# 04_-_CIRCUIT.net
KiCad netlist of a schematic drawn in Altium Designer
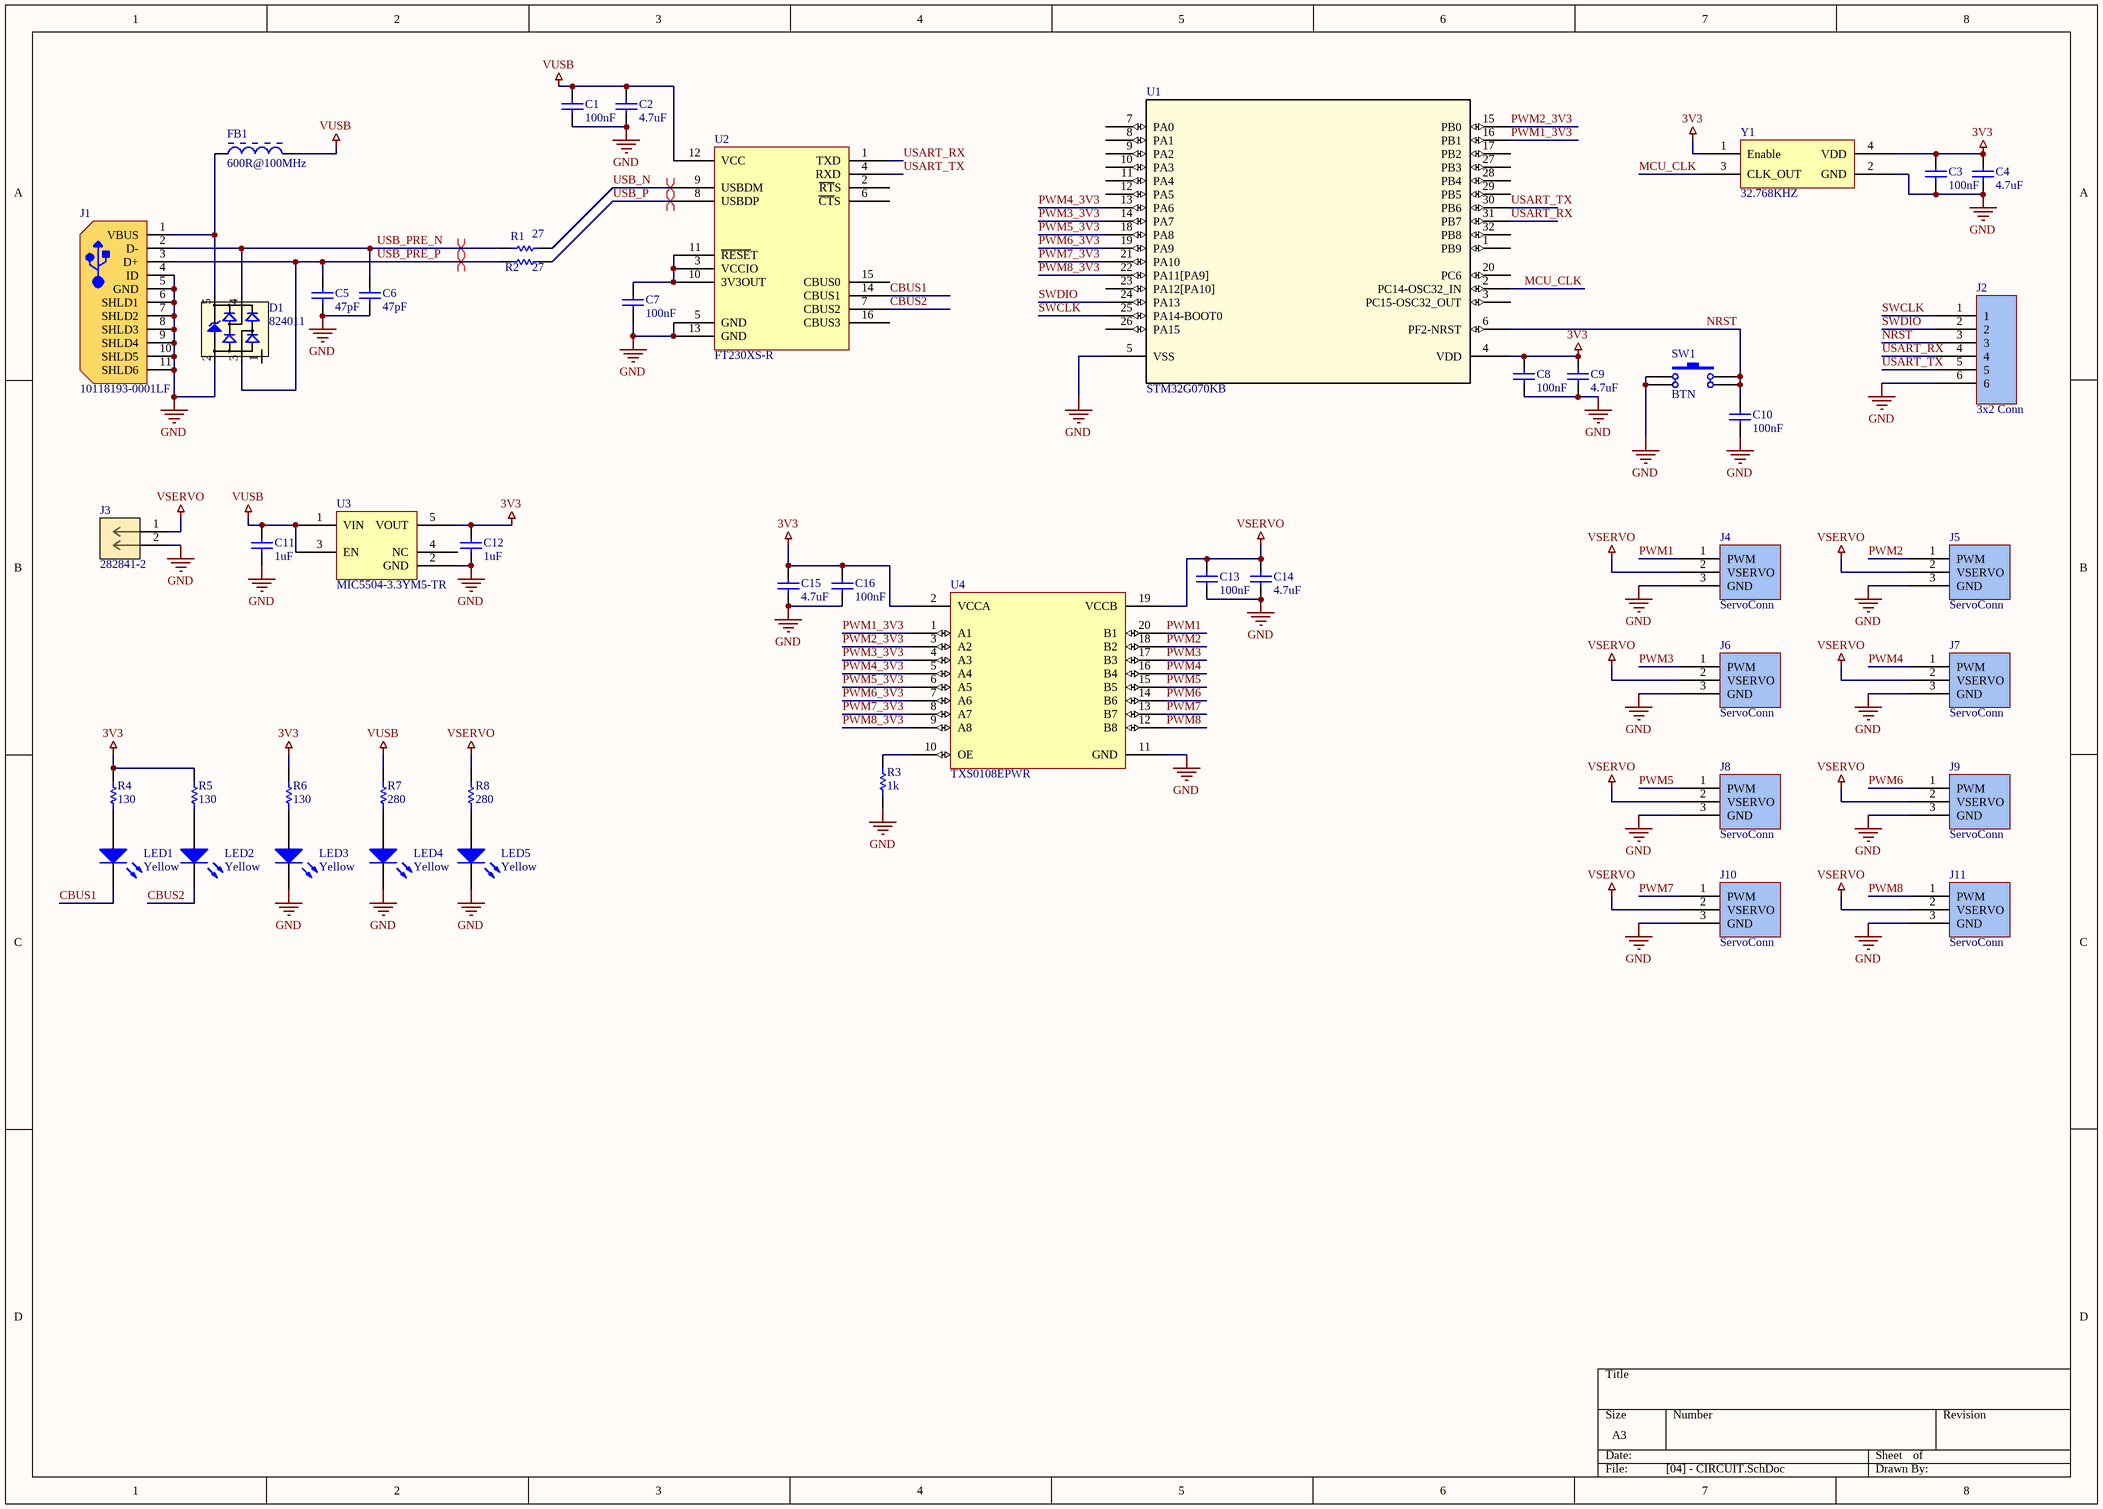
[diagram p0: [04] - CIRCUIT.SchDoc]

(export (version "E")
  (design (tool "Eeschema 10.0.6"))
  (components
    (comp (ref "C1")
      (value "100nF")
      (footprint "CAPC2012X10N")
      (description "CAP CER 0.1UF 100V X7R 0805")
      (libsource (lib "roboARM") (part "GCD21BR72A104KA01L"))
    )
    (comp (ref "C2")
      (value "4.7uF")
      (footprint "CAPC2012X10N")
      (description "Cap Ceramic 4.7uF 50V X5R 10% SMD 0805 85C Embossed T/R")
      (fields (field (name "TOLERANCE") "10%"))
      (libsource (lib "*") (part "GRM21BR61H475KE51L"))
    )
    (comp (ref "C3")
      (value "100nF")
      (footprint "CAPC2012X10N")
      (description "CAP CER 0.1UF 100V X7R 0805")
      (libsource (lib "roboARM") (part "GCD21BR72A104KA01L"))
    )
    (comp (ref "C4")
      (value "4.7uF")
      (footprint "CAPC2012X10N")
      (description "Cap Ceramic 4.7uF 50V X5R 10% SMD 0805 85C Embossed T/R")
      (fields (field (name "TOLERANCE") "10%"))
      (libsource (lib "*") (part "GRM21BR61H475KE51L"))
    )
    (comp (ref "C5")
      (value "47pF")
      (footprint "CAPC2012X10N")
      (fields (field (name "VOLTAGE") "200V") (field (name "TOLERANCE") "5%"))
      (libsource (lib "roboARM") (part "GRM21A5C2D470JW01D"))
    )
    (comp (ref "C6")
      (value "47pF")
      (footprint "CAPC2012X10N")
      (fields (field (name "VOLTAGE") "200V") (field (name "TOLERANCE") "5%"))
      (libsource (lib "roboARM") (part "GRM21A5C2D470JW01D"))
    )
    (comp (ref "C7")
      (value "100nF")
      (footprint "CAPC2012X10N")
      (description "CAP CER 0.1UF 100V X7R 0805")
      (libsource (lib "roboARM") (part "GCD21BR72A104KA01L"))
    )
    (comp (ref "C8")
      (value "100nF")
      (footprint "CAPC2012X10N")
      (description "CAP CER 0.1UF 100V X7R 0805")
      (libsource (lib "roboARM") (part "GCD21BR72A104KA01L"))
    )
    (comp (ref "C9")
      (value "4.7uF")
      (footprint "CAPC2012X10N")
      (description "Cap Ceramic 4.7uF 50V X5R 10% SMD 0805 85C Embossed T/R")
      (fields (field (name "TOLERANCE") "10%"))
      (libsource (lib "*") (part "GRM21BR61H475KE51L"))
    )
    (comp (ref "C10")
      (value "100nF")
      (footprint "CAPC2012X10N")
      (description "CAP CER 0.1UF 100V X7R 0805")
      (libsource (lib "roboARM") (part "GCD21BR72A104KA01L"))
    )
    (comp (ref "C11")
      (value "CL21B105KOFNNNG")
      (footprint "CAPC2012X10N")
      (description "Cap Ceramic 1uF 16V X7R 10% SMD 0805 125C Embossed T/R")
      (fields
        (field (name "MANUFACTURER") "Samsung")
        (field (name "TOLERANCE") "10%")
        (field (name "CAPACITANCE") "1uF")
      )
      (libsource (lib "roboARM") (part "CL21B105KOFNNNG"))
    )
    (comp (ref "C12")
      (value "CL21B105KOFNNNG")
      (footprint "CAPC2012X10N")
      (description "Cap Ceramic 1uF 16V X7R 10% SMD 0805 125C Embossed T/R")
      (fields
        (field (name "MANUFACTURER") "Samsung")
        (field (name "TOLERANCE") "10%")
        (field (name "CAPACITANCE") "1uF")
      )
      (libsource (lib "roboARM") (part "CL21B105KOFNNNG"))
    )
    (comp (ref "C13")
      (value "100nF")
      (footprint "CAPC2012X10N")
      (description "CAP CER 0.1UF 100V X7R 0805")
      (libsource (lib "roboARM") (part "GCD21BR72A104KA01L"))
    )
    (comp (ref "C14")
      (value "4.7uF")
      (footprint "CAPC2012X10N")
      (description "Cap Ceramic 4.7uF 50V X5R 10% SMD 0805 85C Embossed T/R")
      (fields (field (name "TOLERANCE") "10%"))
      (libsource (lib "*") (part "GRM21BR61H475KE51L"))
    )
    (comp (ref "C15")
      (value "4.7uF")
      (footprint "CAPC2012X10N")
      (description "Cap Ceramic 4.7uF 50V X5R 10% SMD 0805 85C Embossed T/R")
      (fields (field (name "TOLERANCE") "10%"))
      (libsource (lib "*") (part "GRM21BR61H475KE51L"))
    )
    (comp (ref "C16")
      (value "100nF")
      (footprint "CAPC2012X10N")
      (description "CAP CER 0.1UF 100V X7R 0805")
      (libsource (lib "roboARM") (part "GCD21BR72A104KA01L"))
    )
    (comp (ref "D1")
      (value "824011")
      (footprint "SOT23_5L")
      (description "TVS Diode WE-TVS-HS, VRWM=5V")
      (fields (field (name "MANUFACTURER") "Wuerth Elektronik"))
      (libsource (lib "roboARM") (part "CMP-1474-00002-1"))
    )
    (comp (ref "FB1")
      (value "600R@100MHz")
      (footprint "LIRD-MI0805K601R-10-2_V")
      (description "FERRITE BEAD 600 OHM 0805 1LN")
      (libsource (lib "roboARM") (part "MI0805K601R-10"))
    )
    (comp (ref "J1")
      (value "10118193-0001LF")
      (footprint "FCI-10118193-0001LF-5_V")
      (description "Micro USB B Type Receptacle, -55 to 85 degC, 5-Pin SMD, RoHS, Tape and Reel")
      (fields (field (name "MANUFACTURER") "FCI"))
      (libsource (lib "roboARM") (part "CMP-2000-05119-1"))
    )
    (comp (ref "J2")
      (value "3x2 Conn")
      (footprint "61200621721")
      (libsource (lib "roboARM") (part "61200621721"))
    )
    (comp (ref "J3")
      (value "282841-2")
      (footprint "Clema")
      (description "No Description Available")
      (fields (field (name "COPYRIGHT") "Copyright (C) 2016 Accelerated Designs. All rights reserved"))
      (libsource (lib "roboARM") (part "282841-2"))
    )
    (comp (ref "J4")
      (value "ServoConn")
      (footprint "3_POS_PIN")
      (description "CONN HEADER VERT 3POS 2.54MM")
      (libsource (lib "roboARM") (part "PR20203VBNN"))
    )
    (comp (ref "J5")
      (value "ServoConn")
      (footprint "3_POS_PIN")
      (description "CONN HEADER VERT 3POS 2.54MM")
      (libsource (lib "roboARM") (part "PR20203VBNN"))
    )
    (comp (ref "J6")
      (value "ServoConn")
      (footprint "3_POS_PIN")
      (description "CONN HEADER VERT 3POS 2.54MM")
      (libsource (lib "roboARM") (part "PR20203VBNN"))
    )
    (comp (ref "J7")
      (value "ServoConn")
      (footprint "3_POS_PIN")
      (description "CONN HEADER VERT 3POS 2.54MM")
      (libsource (lib "roboARM") (part "PR20203VBNN"))
    )
    (comp (ref "J8")
      (value "ServoConn")
      (footprint "3_POS_PIN")
      (description "CONN HEADER VERT 3POS 2.54MM")
      (libsource (lib "roboARM") (part "PR20203VBNN"))
    )
    (comp (ref "J9")
      (value "ServoConn")
      (footprint "3_POS_PIN")
      (description "CONN HEADER VERT 3POS 2.54MM")
      (libsource (lib "roboARM") (part "PR20203VBNN"))
    )
    (comp (ref "J10")
      (value "ServoConn")
      (footprint "3_POS_PIN")
      (description "CONN HEADER VERT 3POS 2.54MM")
      (libsource (lib "roboARM") (part "PR20203VBNN"))
    )
    (comp (ref "J11")
      (value "ServoConn")
      (footprint "3_POS_PIN")
      (description "CONN HEADER VERT 3POS 2.54MM")
      (libsource (lib "roboARM") (part "PR20203VBNN"))
    )
    (comp (ref "LED1")
      (value "Yellow")
      (footprint "LED_0805")
      (description "SMD mono-color Chip LED, WL-SMCW, Yellow")
      (fields (field (name "MANUFACTURER") "Wuerth Elektronik") (field (name "PARTNUMBER") "150080YS75000"))
      (libsource (lib "roboARM") (part "CMP-1426-00012-1"))
    )
    (comp (ref "LED2")
      (value "Yellow")
      (footprint "LED_0805")
      (description "SMD mono-color Chip LED, WL-SMCW, Yellow")
      (fields (field (name "MANUFACTURER") "Wuerth Elektronik") (field (name "PARTNUMBER") "150080YS75000"))
      (libsource (lib "roboARM") (part "CMP-1426-00012-1"))
    )
    (comp (ref "LED3")
      (value "Yellow")
      (footprint "LED_0805")
      (description "SMD mono-color Chip LED, WL-SMCW, Yellow")
      (fields (field (name "MANUFACTURER") "Wuerth Elektronik") (field (name "PARTNUMBER") "150080YS75000"))
      (libsource (lib "roboARM") (part "CMP-1426-00012-1"))
    )
    (comp (ref "LED4")
      (value "Yellow")
      (footprint "LED_0805")
      (description "SMD mono-color Chip LED, WL-SMCW, Yellow")
      (fields (field (name "MANUFACTURER") "Wuerth Elektronik") (field (name "PARTNUMBER") "150080YS75000"))
      (libsource (lib "roboARM") (part "CMP-1426-00012-1"))
    )
    (comp (ref "LED5")
      (value "Yellow")
      (footprint "LED_0805")
      (description "SMD mono-color Chip LED, WL-SMCW, Yellow")
      (fields (field (name "MANUFACTURER") "Wuerth Elektronik") (field (name "PARTNUMBER") "150080YS75000"))
      (libsource (lib "roboARM") (part "CMP-1426-00012-1"))
    )
    (comp (ref "R1")
      (value "27")
      (footprint "RESC2012X07N")
      (description "RES 27 OHM 1/8W 1% 0805")
      (fields (field (name "TOLERANCE") "1%"))
      (libsource (lib "roboARM") (part "RMCF0805FT27R0"))
    )
    (comp (ref "R2")
      (value "27")
      (footprint "RESC2012X07N")
      (description "RES 27 OHM 1/8W 1% 0805")
      (fields (field (name "TOLERANCE") "1%"))
      (libsource (lib "roboARM") (part "RMCF0805FT27R0"))
    )
    (comp (ref "R3")
      (value "1k")
      (footprint "RESC2012X07N")
      (description "RES 1K OHM 5% 1/8W 0805")
      (fields
        (field (name "MANUFACTURER") "Stackpole Electronics")
        (field (name "MANUFACTURER PART NUMBER") "RMCF0805JT1K00")
      )
      (libsource (lib "roboARM") (part "RMCF0805JT1K00"))
    )
    (comp (ref "R4")
      (value "130")
      (footprint "RESC2012X07N")
      (description "Res Thick Film 0805 130 Ohm 1% 0.125W(1/8W) ±100ppm/C Pad SMD Automotive T/R")
      (fields (field (name "TOLERANCE") "1%"))
      (libsource (lib "roboARM") (part "RMCF0805FT130R"))
    )
    (comp (ref "R5")
      (value "130")
      (footprint "RESC2012X07N")
      (description "Res Thick Film 0805 130 Ohm 1% 0.125W(1/8W) ±100ppm/C Pad SMD Automotive T/R")
      (fields (field (name "TOLERANCE") "1%"))
      (libsource (lib "roboARM") (part "RMCF0805FT130R"))
    )
    (comp (ref "R6")
      (value "130")
      (footprint "RESC2012X07N")
      (description "Res Thick Film 0805 130 Ohm 1% 0.125W(1/8W) ±100ppm/C Pad SMD Automotive T/R")
      (fields (field (name "TOLERANCE") "1%"))
      (libsource (lib "roboARM") (part "RMCF0805FT130R"))
    )
    (comp (ref "R7")
      (value "280")
      (footprint "RESC2012X07N")
      (description "Res Thick Film 0805 280 Ohm 1% 0.125W(1/8W) ±100ppm/C Pad SMD Automotive T/R")
      (fields (field (name "TOLERANCE") "1%"))
      (libsource (lib "roboARM") (part "RMCF0805FT280R"))
    )
    (comp (ref "R8")
      (value "280")
      (description "Res Thick Film 0805 280 Ohm 1% 0.125W(1/8W) ±100ppm/C Pad SMD Automotive T/R")
      (fields (field (name "TOLERANCE") "1%"))
      (libsource (lib "roboARM") (part "RMCF0805FT280R"))
    )
    (comp (ref "SW1")
      (value "BTN")
      (footprint "Button")
      (description "INWALL LENS COVER , WHITE , 6 (")
      (fields
        (field (name "MANUFACTURER") "ITT C&K")
        (field (name "MANUFACTURER PART NUMBER") "PTS647SK70SMTR2LFS")
      )
      (libsource (lib "roboARM") (part "PTS647SK70SMTR2LFS"))
    )
    (comp (ref "U1")
      (value "STM32G070KB")
      (footprint "LQFP-32")
      (fields
        (field (name "MANUFACTURER_PART_NUMBER") "STM32G0_LQFP32_T1")
        (field (name "COPYRIGHT") "Copyright (C) 2016 Accelerated Designs. All rights reserved")
      )
      (libsource (lib "roboARM") (part "STM32G070KB"))
    )
    (comp (ref "U2")
      (value "FT230XS-R")
      (footprint "SOP64P600X175-16N")
      (description "IC USB SERIAL BASIC UART 16SSOP")
      (libsource (lib "roboARM") (part "FT230XS-R"))
    )
    (comp (ref "U3")
      (value "MIC5504-3.3YM5-TR")
      (footprint "SOT95P280X145-5N")
      (description "LDO VOLT REG, 0.3A, 3.3V, SOT-23-5")
      (libsource (lib "roboARM") (part "MIC5504-3.3YM5-TR"))
    )
    (comp (ref "U4")
      (value "TXS0108EPWR")
      (footprint "TSOP65P640X120-20N")
      (description "TRANSLATOR, VOLTAGE, 8BIT, 20TSSOP")
      (libsource (lib "roboARM") (part "TXS0108EPWR"))
    )
    (comp (ref "Y1")
      (value "32.768KHZ")
      (footprint "KX251")
      (description "OSCILLATOR XO 32.768KHZ CMOS SMD")
      (libsource (lib "roboARM") (part "KX2511A0032.768000"))
    )
  )
  (nets
    (net (code "1") (name "/CBUS1") (class "Default")
      (node (ref "LED1") (pin "1") (pinfunction "K_1") (pintype "passive"))
      (node (ref "U2") (pin "14") (pinfunction "CBUS1_14") (pintype "passive"))
    )
    (net (code "2") (name "/CBUS2") (class "Default")
      (node (ref "LED2") (pin "1") (pinfunction "K_1") (pintype "passive"))
      (node (ref "U2") (pin "7") (pinfunction "CBUS2_7") (pintype "passive"))
    )
    (net (code "3") (name "/MCU_CLK") (class "Default")
      (node (ref "U1") (pin "2") (pinfunction "PC14-OSC32_IN_2") (pintype "bidirectional"))
      (node (ref "Y1") (pin "3") (pinfunction "CLK_OUT_3") (pintype "passive"))
    )
    (net (code "4") (name "/NRST") (class "Default")
      (node (ref "C10") (pin "2") (pinfunction "2_2") (pintype "passive"))
      (node (ref "J2") (pin "3") (pinfunction "3_3") (pintype "passive"))
      (node (ref "SW1") (pin "3") (pinfunction "2_3") (pintype "passive"))
      (node (ref "SW1") (pin "4") (pinfunction "3_4") (pintype "passive"))
      (node (ref "U1") (pin "6") (pinfunction "PF2-NRST_6") (pintype "bidirectional"))
    )
    (net (code "5") (name "/PWM1") (class "Default")
      (node (ref "J4") (pin "1") (pinfunction "PWM_1") (pintype "passive"))
      (node (ref "U4") (pin "20") (pinfunction "B1_20") (pintype "bidirectional"))
    )
    (net (code "6") (name "/PWM1_3V3") (class "Default")
      (node (ref "U1") (pin "16") (pinfunction "PB1_16") (pintype "bidirectional"))
      (node (ref "U4") (pin "1") (pinfunction "A1_1") (pintype "bidirectional"))
    )
    (net (code "7") (name "/PWM2") (class "Default")
      (node (ref "J5") (pin "1") (pinfunction "PWM_1") (pintype "passive"))
      (node (ref "U4") (pin "18") (pinfunction "B2_18") (pintype "bidirectional"))
    )
    (net (code "8") (name "/PWM2_3V3") (class "Default")
      (node (ref "U1") (pin "15") (pinfunction "PB0_15") (pintype "bidirectional"))
      (node (ref "U4") (pin "3") (pinfunction "A2_3") (pintype "bidirectional"))
    )
    (net (code "9") (name "/PWM3") (class "Default")
      (node (ref "J6") (pin "1") (pinfunction "PWM_1") (pintype "passive"))
      (node (ref "U4") (pin "17") (pinfunction "B3_17") (pintype "bidirectional"))
    )
    (net (code "10") (name "/PWM3_3V3") (class "Default")
      (node (ref "U1") (pin "14") (pinfunction "PA7_14") (pintype "bidirectional"))
      (node (ref "U4") (pin "4") (pinfunction "A3_4") (pintype "bidirectional"))
    )
    (net (code "11") (name "/PWM4") (class "Default")
      (node (ref "J7") (pin "1") (pinfunction "PWM_1") (pintype "passive"))
      (node (ref "U4") (pin "16") (pinfunction "B4_16") (pintype "bidirectional"))
    )
    (net (code "12") (name "/PWM4_3V3") (class "Default")
      (node (ref "U1") (pin "13") (pinfunction "PA6_13") (pintype "bidirectional"))
      (node (ref "U4") (pin "5") (pinfunction "A4_5") (pintype "bidirectional"))
    )
    (net (code "13") (name "/PWM5") (class "Default")
      (node (ref "J8") (pin "1") (pinfunction "PWM_1") (pintype "passive"))
      (node (ref "U4") (pin "15") (pinfunction "B5_15") (pintype "bidirectional"))
    )
    (net (code "14") (name "/PWM5_3V3") (class "Default")
      (node (ref "U1") (pin "18") (pinfunction "PA8_18") (pintype "bidirectional"))
      (node (ref "U4") (pin "6") (pinfunction "A5_6") (pintype "bidirectional"))
    )
    (net (code "15") (name "/PWM6") (class "Default")
      (node (ref "J9") (pin "1") (pinfunction "PWM_1") (pintype "passive"))
      (node (ref "U4") (pin "14") (pinfunction "B6_14") (pintype "bidirectional"))
    )
    (net (code "16") (name "/PWM6_3V3") (class "Default")
      (node (ref "U1") (pin "19") (pinfunction "PA9_19") (pintype "bidirectional"))
      (node (ref "U4") (pin "7") (pinfunction "A6_7") (pintype "bidirectional"))
    )
    (net (code "17") (name "/PWM7") (class "Default")
      (node (ref "J10") (pin "1") (pinfunction "PWM_1") (pintype "passive"))
      (node (ref "U4") (pin "13") (pinfunction "B7_13") (pintype "bidirectional"))
    )
    (net (code "18") (name "/PWM7_3V3") (class "Default")
      (node (ref "U1") (pin "21") (pinfunction "PA10_21") (pintype "bidirectional"))
      (node (ref "U4") (pin "8") (pinfunction "A7_8") (pintype "bidirectional"))
    )
    (net (code "19") (name "/PWM8") (class "Default")
      (node (ref "J11") (pin "1") (pinfunction "PWM_1") (pintype "passive"))
      (node (ref "U4") (pin "12") (pinfunction "B8_12") (pintype "bidirectional"))
    )
    (net (code "20") (name "/PWM8_3V3") (class "Default")
      (node (ref "U1") (pin "22") (pinfunction "PA11[PA9]_22") (pintype "bidirectional"))
      (node (ref "U4") (pin "9") (pinfunction "A8_9") (pintype "bidirectional"))
    )
    (net (code "21") (name "/SWCLK") (class "Default")
      (node (ref "J2") (pin "1") (pinfunction "1_1") (pintype "passive"))
      (node (ref "U1") (pin "25") (pinfunction "PA14-BOOT0_25") (pintype "bidirectional"))
    )
    (net (code "22") (name "/SWDIO") (class "Default")
      (node (ref "J2") (pin "2") (pinfunction "2_2") (pintype "passive"))
      (node (ref "U1") (pin "24") (pinfunction "PA13_24") (pintype "bidirectional"))
    )
    (net (code "23") (name "/USART_RX") (class "Default")
      (node (ref "J2") (pin "4") (pinfunction "4_4") (pintype "passive"))
      (node (ref "U1") (pin "31") (pinfunction "PB7_31") (pintype "bidirectional"))
      (node (ref "U2") (pin "1") (pinfunction "TXD_1") (pintype "passive"))
    )
    (net (code "24") (name "/USART_TX") (class "Default")
      (node (ref "J2") (pin "5") (pinfunction "5_5") (pintype "passive"))
      (node (ref "U1") (pin "30") (pinfunction "PB6_30") (pintype "bidirectional"))
      (node (ref "U2") (pin "4") (pinfunction "RXD_4") (pintype "passive"))
    )
    (net (code "25") (name "/USB_N") (class "Default")
      (node (ref "R1") (pin "2") (pinfunction "2_2") (pintype "passive"))
      (node (ref "U2") (pin "9") (pinfunction "USBDM_9") (pintype "passive"))
    )
    (net (code "26") (name "/USB_P") (class "Default")
      (node (ref "R2") (pin "2") (pinfunction "2_2") (pintype "passive"))
      (node (ref "U2") (pin "8") (pinfunction "USBDP_8") (pintype "passive"))
    )
    (net (code "27") (name "/USB_PRE_N") (class "Default")
      (node (ref "C6") (pin "2") (pinfunction "2_2") (pintype "passive"))
      (node (ref "D1") (pin "4") (pinfunction "I/O2_4") (pintype "passive"))
      (node (ref "J1") (pin "2") (pinfunction "D-_2") (pintype "passive"))
      (node (ref "R1") (pin "1") (pinfunction "1_1") (pintype "passive"))
    )
    (net (code "28") (name "/USB_PRE_P") (class "Default")
      (node (ref "C5") (pin "2") (pinfunction "2_2") (pintype "passive"))
      (node (ref "D1") (pin "3") (pinfunction "I/O1_3") (pintype "passive"))
      (node (ref "J1") (pin "3") (pinfunction "D+_3") (pintype "passive"))
      (node (ref "R2") (pin "1") (pinfunction "1_1") (pintype "passive"))
    )
    (net (code "29") (name "3V3") (class "Default")
      (node (ref "C12") (pin "2") (pinfunction "2_2") (pintype "passive"))
      (node (ref "C15") (pin "2") (pinfunction "2_2") (pintype "passive"))
      (node (ref "C16") (pin "2") (pinfunction "2_2") (pintype "passive"))
      (node (ref "C3") (pin "2") (pinfunction "2_2") (pintype "passive"))
      (node (ref "C4") (pin "2") (pinfunction "2_2") (pintype "passive"))
      (node (ref "C8") (pin "2") (pinfunction "2_2") (pintype "passive"))
      (node (ref "C9") (pin "2") (pinfunction "2_2") (pintype "passive"))
      (node (ref "R4") (pin "1") (pinfunction "1_1") (pintype "passive"))
      (node (ref "R5") (pin "1") (pinfunction "1_1") (pintype "passive"))
      (node (ref "R6") (pin "1") (pinfunction "1_1") (pintype "passive"))
      (node (ref "U1") (pin "4") (pinfunction "VDD_4") (pintype "power_in"))
      (node (ref "U3") (pin "5") (pinfunction "VOUT_5") (pintype "passive"))
      (node (ref "U4") (pin "2") (pinfunction "VCCA_2") (pintype "power_in"))
      (node (ref "Y1") (pin "1") (pinfunction "Enable_1") (pintype "passive"))
      (node (ref "Y1") (pin "4") (pinfunction "VDD_4") (pintype "passive"))
    )
    (net (code "30") (name "GND") (class "Default")
      (node (ref "C1") (pin "1") (pinfunction "1_1") (pintype "passive"))
      (node (ref "C10") (pin "1") (pinfunction "1_1") (pintype "passive"))
      (node (ref "C11") (pin "1") (pinfunction "1_1") (pintype "passive"))
      (node (ref "C12") (pin "1") (pinfunction "1_1") (pintype "passive"))
      (node (ref "C13") (pin "1") (pinfunction "1_1") (pintype "passive"))
      (node (ref "C14") (pin "1") (pinfunction "1_1") (pintype "passive"))
      (node (ref "C15") (pin "1") (pinfunction "1_1") (pintype "passive"))
      (node (ref "C16") (pin "1") (pinfunction "1_1") (pintype "passive"))
      (node (ref "C2") (pin "1") (pinfunction "1_1") (pintype "passive"))
      (node (ref "C3") (pin "1") (pinfunction "1_1") (pintype "passive"))
      (node (ref "C4") (pin "1") (pinfunction "1_1") (pintype "passive"))
      (node (ref "C5") (pin "1") (pinfunction "1_1") (pintype "passive"))
      (node (ref "C6") (pin "1") (pinfunction "1_1") (pintype "passive"))
      (node (ref "C7") (pin "1") (pinfunction "1_1") (pintype "passive"))
      (node (ref "C8") (pin "1") (pinfunction "1_1") (pintype "passive"))
      (node (ref "C9") (pin "1") (pinfunction "1_1") (pintype "passive"))
      (node (ref "D1") (pin "2") (pinfunction "GND_2") (pintype "passive"))
      (node (ref "J1") (pin "10") (pinfunction "SHLD5_10") (pintype "passive"))
      (node (ref "J1") (pin "11") (pinfunction "SHLD6_11") (pintype "passive"))
      (node (ref "J1") (pin "4") (pinfunction "ID_4") (pintype "passive"))
      (node (ref "J1") (pin "5") (pinfunction "GND_5") (pintype "passive"))
      (node (ref "J1") (pin "6") (pinfunction "SHLD1_6") (pintype "passive"))
      (node (ref "J1") (pin "7") (pinfunction "SHLD2_7") (pintype "passive"))
      (node (ref "J1") (pin "8") (pinfunction "SHLD3_8") (pintype "passive"))
      (node (ref "J1") (pin "9") (pinfunction "SHLD4_9") (pintype "passive"))
      (node (ref "J10") (pin "3") (pinfunction "GND_3") (pintype "passive"))
      (node (ref "J11") (pin "3") (pinfunction "GND_3") (pintype "passive"))
      (node (ref "J2") (pin "6") (pinfunction "6_6") (pintype "passive"))
      (node (ref "J3") (pin "2") (pinfunction "2_2") (pintype "passive"))
      (node (ref "J4") (pin "3") (pinfunction "GND_3") (pintype "passive"))
      (node (ref "J5") (pin "3") (pinfunction "GND_3") (pintype "passive"))
      (node (ref "J6") (pin "3") (pinfunction "GND_3") (pintype "passive"))
      (node (ref "J7") (pin "3") (pinfunction "GND_3") (pintype "passive"))
      (node (ref "J8") (pin "3") (pinfunction "GND_3") (pintype "passive"))
      (node (ref "J9") (pin "3") (pinfunction "GND_3") (pintype "passive"))
      (node (ref "LED3") (pin "1") (pinfunction "K_1") (pintype "passive"))
      (node (ref "LED4") (pin "1") (pinfunction "K_1") (pintype "passive"))
      (node (ref "LED5") (pin "1") (pinfunction "K_1") (pintype "passive"))
      (node (ref "R3") (pin "1") (pinfunction "1_1") (pintype "passive"))
      (node (ref "SW1") (pin "1") (pinfunction "1_1") (pintype "passive"))
      (node (ref "SW1") (pin "2") (pinfunction "1_2") (pintype "passive"))
      (node (ref "U1") (pin "5") (pinfunction "VSS_5") (pintype "power_in"))
      (node (ref "U2") (pin "13") (pinfunction "GND_13") (pintype "passive"))
      (node (ref "U2") (pin "5") (pinfunction "GND_5") (pintype "passive"))
      (node (ref "U3") (pin "2") (pinfunction "GND_2") (pintype "passive"))
      (node (ref "U4") (pin "11") (pinfunction "GND_11") (pintype "power_in"))
      (node (ref "Y1") (pin "2") (pinfunction "GND_2") (pintype "passive"))
    )
    (net (code "31") (name "Net-(D1-VDD)") (class "Default")
      (node (ref "D1") (pin "5") (pinfunction "VDD_5") (pintype "passive"))
      (node (ref "FB1") (pin "1") (pinfunction "1_1") (pintype "passive"))
      (node (ref "J1") (pin "1") (pinfunction "VBUS_1") (pintype "passive"))
    )
    (net (code "32") (name "Net-(LED1-A)") (class "Default")
      (node (ref "LED1") (pin "2") (pinfunction "A_2") (pintype "passive"))
      (node (ref "R4") (pin "2") (pinfunction "2_2") (pintype "passive"))
    )
    (net (code "33") (name "Net-(LED2-A)") (class "Default")
      (node (ref "LED2") (pin "2") (pinfunction "A_2") (pintype "passive"))
      (node (ref "R5") (pin "2") (pinfunction "2_2") (pintype "passive"))
    )
    (net (code "34") (name "Net-(LED3-A)") (class "Default")
      (node (ref "LED3") (pin "2") (pinfunction "A_2") (pintype "passive"))
      (node (ref "R6") (pin "2") (pinfunction "2_2") (pintype "passive"))
    )
    (net (code "35") (name "Net-(LED4-A)") (class "Default")
      (node (ref "LED4") (pin "2") (pinfunction "A_2") (pintype "passive"))
      (node (ref "R7") (pin "1") (pinfunction "1_1") (pintype "passive"))
    )
    (net (code "36") (name "Net-(LED5-A)") (class "Default")
      (node (ref "LED5") (pin "2") (pinfunction "A_2") (pintype "passive"))
      (node (ref "R8") (pin "1") (pinfunction "1_1") (pintype "passive"))
    )
    (net (code "37") (name "Net-(U2-3V3OUT)") (class "Default")
      (node (ref "C7") (pin "2") (pinfunction "2_2") (pintype "passive"))
      (node (ref "U2") (pin "10") (pinfunction "3V3OUT_10") (pintype "passive"))
      (node (ref "U2") (pin "11") (pinfunction "~{RESE}T_11") (pintype "passive"))
      (node (ref "U2") (pin "3") (pinfunction "VCCIO_3") (pintype "passive"))
    )
    (net (code "38") (name "Net-(U4-OE)") (class "Default")
      (node (ref "R3") (pin "2") (pinfunction "2_2") (pintype "passive"))
      (node (ref "U4") (pin "10") (pinfunction "OE_10") (pintype "bidirectional"))
    )
    (net (code "39") (name "VSERVO") (class "Default")
      (node (ref "C13") (pin "2") (pinfunction "2_2") (pintype "passive"))
      (node (ref "C14") (pin "2") (pinfunction "2_2") (pintype "passive"))
      (node (ref "J10") (pin "2") (pinfunction "VSERVO_2") (pintype "passive"))
      (node (ref "J11") (pin "2") (pinfunction "VSERVO_2") (pintype "passive"))
      (node (ref "J3") (pin "1") (pinfunction "1_1") (pintype "passive"))
      (node (ref "J4") (pin "2") (pinfunction "VSERVO_2") (pintype "passive"))
      (node (ref "J5") (pin "2") (pinfunction "VSERVO_2") (pintype "passive"))
      (node (ref "J6") (pin "2") (pinfunction "VSERVO_2") (pintype "passive"))
      (node (ref "J7") (pin "2") (pinfunction "VSERVO_2") (pintype "passive"))
      (node (ref "J8") (pin "2") (pinfunction "VSERVO_2") (pintype "passive"))
      (node (ref "J9") (pin "2") (pinfunction "VSERVO_2") (pintype "passive"))
      (node (ref "R8") (pin "2") (pinfunction "2_2") (pintype "passive"))
      (node (ref "U4") (pin "19") (pinfunction "VCCB_19") (pintype "power_in"))
    )
    (net (code "40") (name "VUSB") (class "Default")
      (node (ref "C1") (pin "2") (pinfunction "2_2") (pintype "passive"))
      (node (ref "C11") (pin "2") (pinfunction "2_2") (pintype "passive"))
      (node (ref "C2") (pin "2") (pinfunction "2_2") (pintype "passive"))
      (node (ref "FB1") (pin "2") (pinfunction "2_2") (pintype "passive"))
      (node (ref "R7") (pin "2") (pinfunction "2_2") (pintype "passive"))
      (node (ref "U2") (pin "12") (pinfunction "VCC_12") (pintype "passive"))
      (node (ref "U3") (pin "1") (pinfunction "VIN_1") (pintype "passive"))
      (node (ref "U3") (pin "3") (pinfunction "EN_3") (pintype "passive"))
    )
    (net (code "41") (name "unconnected-(D1-NC-Pad1)") (class "Default")
      (node (ref "D1") (pin "1") (pinfunction "NC_1") (pintype "passive"))
    )
    (net (code "42") (name "unconnected-(U1-PA0-Pad7)") (class "Default")
      (node (ref "U1") (pin "7") (pinfunction "PA0_7") (pintype "bidirectional"))
    )
    (net (code "43") (name "unconnected-(U1-PA1-Pad8)") (class "Default")
      (node (ref "U1") (pin "8") (pinfunction "PA1_8") (pintype "bidirectional"))
    )
    (net (code "44") (name "unconnected-(U1-PA2-Pad9)") (class "Default")
      (node (ref "U1") (pin "9") (pinfunction "PA2_9") (pintype "bidirectional"))
    )
    (net (code "45") (name "unconnected-(U1-PA3-Pad10)") (class "Default")
      (node (ref "U1") (pin "10") (pinfunction "PA3_10") (pintype "bidirectional"))
    )
    (net (code "46") (name "unconnected-(U1-PA4-Pad11)") (class "Default")
      (node (ref "U1") (pin "11") (pinfunction "PA4_11") (pintype "bidirectional"))
    )
    (net (code "47") (name "unconnected-(U1-PA5-Pad12)") (class "Default")
      (node (ref "U1") (pin "12") (pinfunction "PA5_12") (pintype "bidirectional"))
    )
    (net (code "48") (name "unconnected-(U1-PA12[PA10]-Pad23)") (class "Default")
      (node (ref "U1") (pin "23") (pinfunction "PA12[PA10]_23") (pintype "bidirectional"))
    )
    (net (code "49") (name "unconnected-(U1-PA15-Pad26)") (class "Default")
      (node (ref "U1") (pin "26") (pinfunction "PA15_26") (pintype "bidirectional"))
    )
    (net (code "50") (name "unconnected-(U1-PB2-Pad17)") (class "Default")
      (node (ref "U1") (pin "17") (pinfunction "PB2_17") (pintype "bidirectional"))
    )
    (net (code "51") (name "unconnected-(U1-PB3-Pad27)") (class "Default")
      (node (ref "U1") (pin "27") (pinfunction "PB3_27") (pintype "bidirectional"))
    )
    (net (code "52") (name "unconnected-(U1-PB4-Pad28)") (class "Default")
      (node (ref "U1") (pin "28") (pinfunction "PB4_28") (pintype "bidirectional"))
    )
    (net (code "53") (name "unconnected-(U1-PB5-Pad29)") (class "Default")
      (node (ref "U1") (pin "29") (pinfunction "PB5_29") (pintype "bidirectional"))
    )
    (net (code "54") (name "unconnected-(U1-PB8-Pad32)") (class "Default")
      (node (ref "U1") (pin "32") (pinfunction "PB8_32") (pintype "bidirectional"))
    )
    (net (code "55") (name "unconnected-(U1-PB9-Pad1)") (class "Default")
      (node (ref "U1") (pin "1") (pinfunction "PB9_1") (pintype "bidirectional"))
    )
    (net (code "56") (name "unconnected-(U1-PC6-Pad20)") (class "Default")
      (node (ref "U1") (pin "20") (pinfunction "PC6_20") (pintype "bidirectional"))
    )
    (net (code "57") (name "unconnected-(U1-PC15-OSC32_OUT-Pad3)") (class "Default")
      (node (ref "U1") (pin "3") (pinfunction "PC15-OSC32_OUT_3") (pintype "bidirectional"))
    )
    (net (code "58") (name "unconnected-(U2-CBUS0-Pad15)") (class "Default")
      (node (ref "U2") (pin "15") (pinfunction "CBUS0_15") (pintype "passive"))
    )
    (net (code "59") (name "unconnected-(U2-CBUS3-Pad16)") (class "Default")
      (node (ref "U2") (pin "16") (pinfunction "CBUS3_16") (pintype "passive"))
    )
    (net (code "60") (name "unconnected-(U2-~{CT}S-Pad6)") (class "Default")
      (node (ref "U2") (pin "6") (pinfunction "~{CT}S_6") (pintype "passive"))
    )
    (net (code "61") (name "unconnected-(U2-~{RT}S-Pad2)") (class "Default")
      (node (ref "U2") (pin "2") (pinfunction "~{RT}S_2") (pintype "passive"))
    )
    (net (code "62") (name "unconnected-(U3-NC-Pad4)") (class "Default")
      (node (ref "U3") (pin "4") (pinfunction "NC_4") (pintype "passive"))
    )
  )
)
